# ESP8266_ATM90E26_Emon.net
KiCad netlist of a schematic drawn in EAGLE
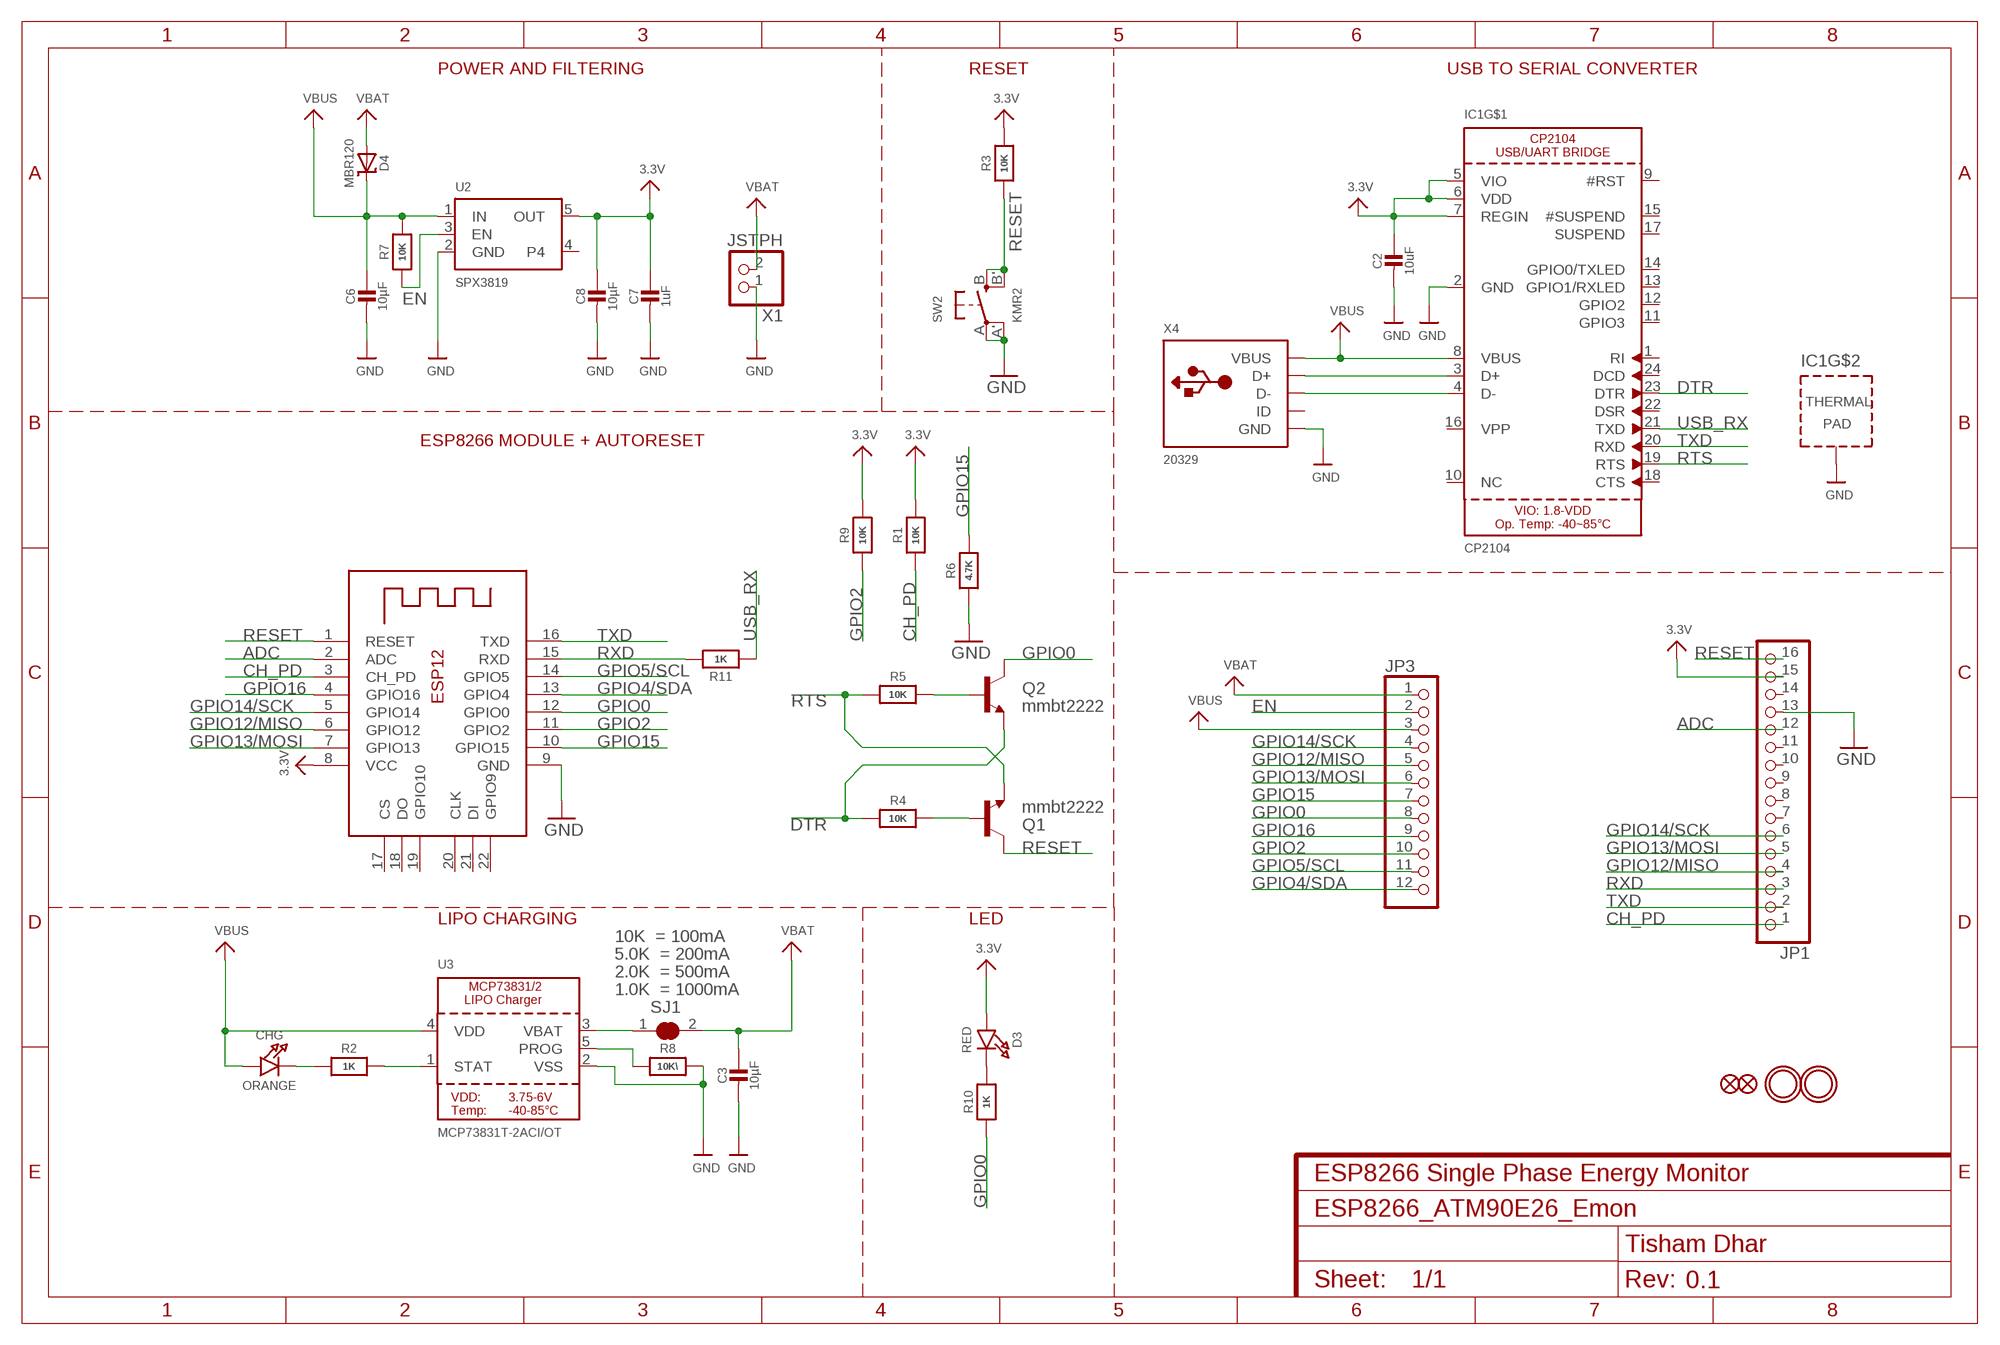
[diagram p0: schematic, sheet 1, part 1 of 2]
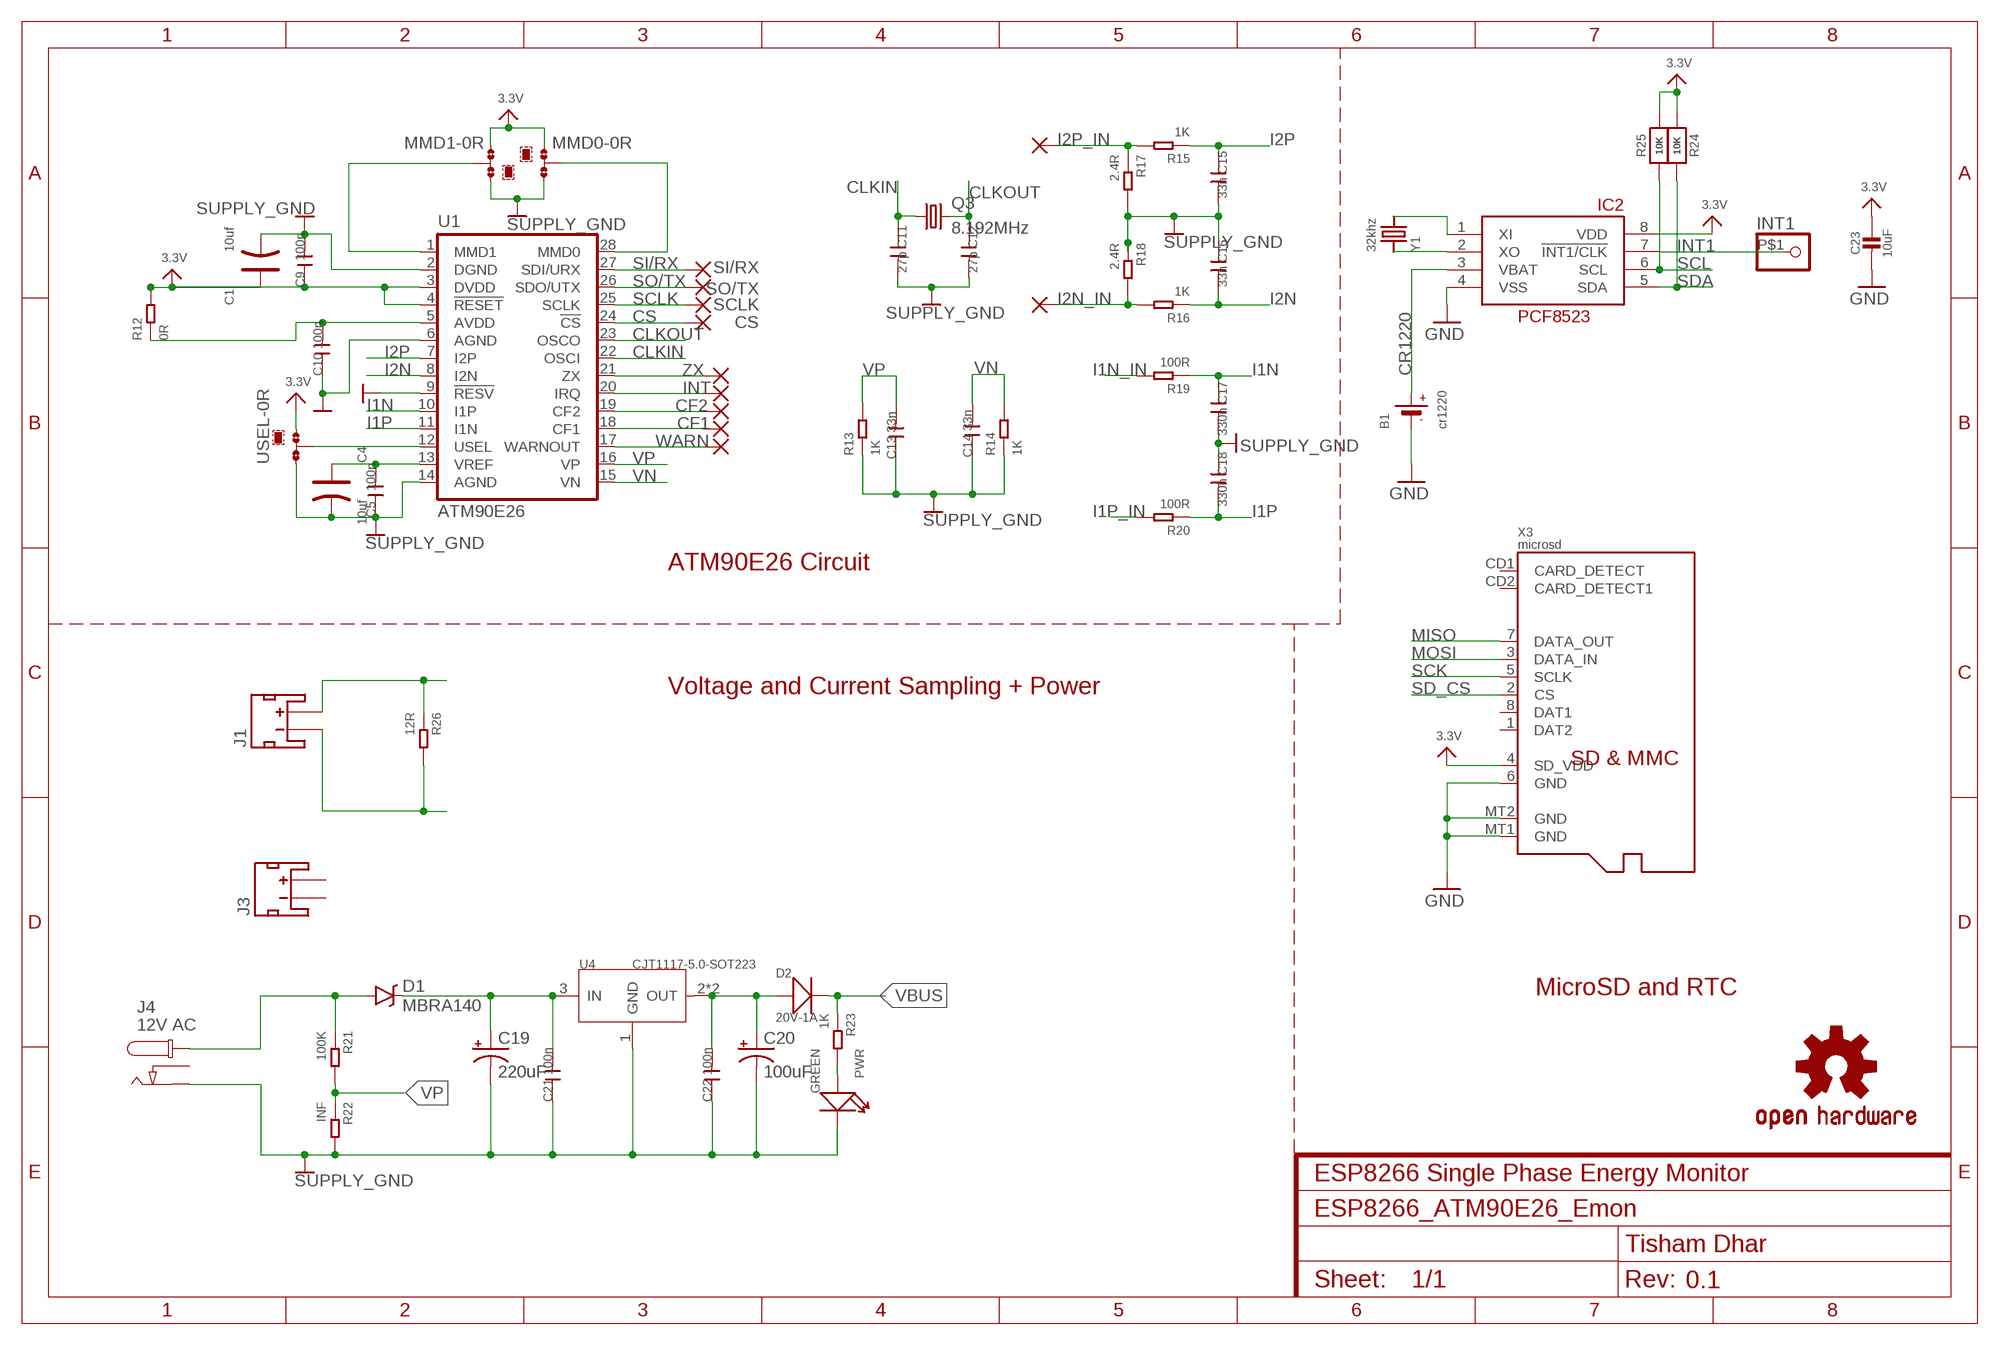
[diagram p1: schematic, sheet 1, part 2 of 2]

(export (version "E")
  (design (tool "Eeschema 10.0.6"))
  (components
    (comp (ref "B1")
      (value "cr1220")
      (footprint "eagle-import:CR1220")
      (libsource (lib "eagle-import") (part "BATTERYCR1220_SMT"))
    )
    (comp (ref "C1")
      (value "10uf")
      (footprint "eagle-import:AVX-A")
      (fields (field (name "MPN") "TAJA226*010#NJ"))
      (libsource (lib "eagle-import") (part "TANTALUM-SMD-22UF-10V(AVX-A)"))
    )
    (comp (ref "C2")
      (value "10uF")
      (footprint "eagle-import:0603-NO")
      (libsource (lib "eagle-import") (part "CAP_CERAMIC0603_NO"))
    )
    (comp (ref "C3")
      (value "10µF")
      (footprint "eagle-import:0603-NO")
      (libsource (lib "eagle-import") (part "CAP_CERAMIC0603_NO"))
    )
    (comp (ref "C4")
      (value "10uf")
      (footprint "eagle-import:AVX-A")
      (fields (field (name "MPN") "TAJA226*010#NJ"))
      (libsource (lib "eagle-import") (part "TANTALUM-SMD-22UF-10V(AVX-A)"))
    )
    (comp (ref "C5")
      (value "100n")
      (footprint "eagle-import:C0603")
      (libsource (lib "eagle-import") (part "C-0603"))
    )
    (comp (ref "C6")
      (value "10µF")
      (footprint "eagle-import:0603-NO")
      (libsource (lib "eagle-import") (part "CAP_CERAMIC0603_NO"))
    )
    (comp (ref "C7")
      (value "1uF")
      (footprint "eagle-import:0603-NO")
      (libsource (lib "eagle-import") (part "CAP_CERAMIC0603_NO"))
    )
    (comp (ref "C8")
      (value "10µF")
      (footprint "eagle-import:0603-NO")
      (libsource (lib "eagle-import") (part "CAP_CERAMIC0603_NO"))
    )
    (comp (ref "C9")
      (value "100n")
      (footprint "eagle-import:C0603")
      (libsource (lib "eagle-import") (part "C-0603"))
    )
    (comp (ref "C10")
      (value "100n")
      (footprint "eagle-import:C0603")
      (libsource (lib "eagle-import") (part "C-0603"))
    )
    (comp (ref "C11")
      (value "27p")
      (footprint "eagle-import:C0603")
      (libsource (lib "eagle-import") (part "C-0603"))
    )
    (comp (ref "C12")
      (value "27p")
      (footprint "eagle-import:C0603")
      (libsource (lib "eagle-import") (part "C-0603"))
    )
    (comp (ref "C13")
      (value "33n")
      (footprint "eagle-import:C0603")
      (libsource (lib "eagle-import") (part "C-0603"))
    )
    (comp (ref "C14")
      (value "33n")
      (footprint "eagle-import:C0603")
      (libsource (lib "eagle-import") (part "C-0603"))
    )
    (comp (ref "C15")
      (value "33n")
      (footprint "eagle-import:C0603")
      (libsource (lib "eagle-import") (part "C-0603"))
    )
    (comp (ref "C16")
      (value "33n")
      (footprint "eagle-import:C0603")
      (libsource (lib "eagle-import") (part "C-0603"))
    )
    (comp (ref "C17")
      (value "330n")
      (footprint "eagle-import:C0603")
      (libsource (lib "eagle-import") (part "C-0603"))
    )
    (comp (ref "C18")
      (value "330n")
      (footprint "eagle-import:C0603")
      (libsource (lib "eagle-import") (part "C-0603"))
    )
    (comp (ref "C19")
      (value "220uF")
      (footprint "eagle-import:140CLH-1010")
      (libsource (lib "eagle-import") (part "CPOL-US140CLH-1010"))
    )
    (comp (ref "C20")
      (value "100uF")
      (footprint "eagle-import:153CLV-0605")
      (libsource (lib "eagle-import") (part "CPOL-US153CLV-0605"))
    )
    (comp (ref "C21")
      (value "100n")
      (footprint "eagle-import:C0603")
      (libsource (lib "eagle-import") (part "C-0603"))
    )
    (comp (ref "C22")
      (value "100n")
      (footprint "eagle-import:C0603")
      (libsource (lib "eagle-import") (part "C-0603"))
    )
    (comp (ref "C23")
      (value "10uF")
      (footprint "eagle-import:0603-NO")
      (libsource (lib "eagle-import") (part "CAP_CERAMIC0603_NO"))
    )
    (comp (ref "CF1")
      (value "WIREPADSMD1,27-254")
      (footprint "eagle-import:SMD1,27-2,54")
      (libsource (lib "eagle-import") (part "WIREPADSMD1,27-254"))
    )
    (comp (ref "CF2")
      (value "WIREPADSMD1,27-254")
      (footprint "eagle-import:SMD1,27-2,54")
      (libsource (lib "eagle-import") (part "WIREPADSMD1,27-254"))
    )
    (comp (ref "CHG")
      (value "ORANGE")
      (footprint "eagle-import:CHIPLED_0603_NOOUTLINE")
      (libsource (lib "eagle-import") (part "LED0603_NOOUTLINE"))
    )
    (comp (ref "CS")
      (value "WIREPADSMD1,27-254")
      (footprint "eagle-import:SMD1,27-2,54")
      (libsource (lib "eagle-import") (part "WIREPADSMD1,27-254"))
    )
    (comp (ref "D1")
      (value "MBRA140")
      (footprint "eagle-import:SMA-DIODE")
      (libsource (lib "eagle-import") (part "MBRA140"))
    )
    (comp (ref "D2")
      (value "20V-1A")
      (footprint "eagle-import:SOD-123")
      (fields (field (name "MPN") "B5819W"))
      (libsource (lib "eagle-import") (part "SMD-DIODE-SCHOTTKY-20V-1A(SOD-123)"))
    )
    (comp (ref "D3")
      (value "RED")
      (footprint "eagle-import:CHIPLED_0805_NOOUTLINE")
      (libsource (lib "eagle-import") (part "LED0805_NOOUTLINE"))
    )
    (comp (ref "D4")
      (value "MBR120")
      (footprint "eagle-import:SOD-123")
      (libsource (lib "eagle-import") (part "DIODE-SCHOTTKYSOD-123"))
    )
    (comp (ref "I2N_IN")
      (value "WIREPADSMD1,27-254")
      (footprint "eagle-import:SMD1,27-2,54")
      (libsource (lib "eagle-import") (part "WIREPADSMD1,27-254"))
    )
    (comp (ref "I2P_IN")
      (value "WIREPADSMD1,27-254")
      (footprint "eagle-import:SMD1,27-2,54")
      (libsource (lib "eagle-import") (part "WIREPADSMD1,27-254"))
    )
    (comp (ref "IC1")
      (value "CP2104")
      (footprint "eagle-import:QFN24_4MM_SMSC")
      (libsource (lib "eagle-import") (part "CP2104"))
    )
    (comp (ref "IC2")
      (value "RTC_PCF8523T")
      (footprint "eagle-import:SOIC8_150MIL")
      (libsource (lib "eagle-import") (part "RTC_PCF8523T"))
    )
    (comp (ref "INT")
      (value "WIREPADSMD1,27-254")
      (footprint "eagle-import:SMD1,27-2,54")
      (libsource (lib "eagle-import") (part "WIREPADSMD1,27-254"))
    )
    (comp (ref "INT1")
      (value "HEADER-1X1-SMD-MASKHELD_1X2MM")
      (footprint "eagle-import:1X01_SMD_MASKHELD_1X2MM")
      (libsource (lib "eagle-import") (part "HEADER-1X1-SMD-MASKHELD_1X2MM"))
    )
    (comp (ref "J1")
      (value "JST_2MM_MALE")
      (footprint "eagle-import:JST-2-SMD")
      (libsource (lib "eagle-import") (part "JST_2MM_MALE"))
    )
    (comp (ref "J3")
      (value "JST_2MM_MALE")
      (footprint "eagle-import:JST-2-SMD")
      (libsource (lib "eagle-import") (part "JST_2MM_MALE"))
    )
    (comp (ref "J4")
      (value "12V AC")
      (footprint "eagle-import:DC_BARREL_JACK_SMD_2MM")
      (libsource (lib "eagle-import") (part "CON_DC_M-DC_SMD"))
    )
    (comp (ref "JP1")
      (value "HEADER-1X16ROUND")
      (footprint "eagle-import:1X16_ROUND")
      (libsource (lib "eagle-import") (part "HEADER-1X16ROUND"))
    )
    (comp (ref "JP3")
      (value "HEADER-1X12")
      (footprint "eagle-import:1X12_ROUND")
      (libsource (lib "eagle-import") (part "HEADER-1X12"))
    )
    (comp (ref "LOGO1")
      (value "OSHW-LOGOS")
      (footprint "eagle-import:OSHW-LOGO-S")
      (libsource (lib "eagle-import") (part "OSHW-LOGOS"))
    )
    (comp (ref "MMD0")
      (value "0R-JUMPA")
      (footprint "eagle-import:A0R-JMP")
      (libsource (lib "eagle-import") (part "0R-JUMPA"))
    )
    (comp (ref "MMD1")
      (value "0R-JUMPA")
      (footprint "eagle-import:A0R-JMP")
      (libsource (lib "eagle-import") (part "0R-JUMPA"))
    )
    (comp (ref "PWR")
      (value "GREEN")
      (footprint "eagle-import:LED-0603")
      (libsource (lib "eagle-import") (part "LED'0603'"))
    )
    (comp (ref "Q1")
      (value "mmbt2222")
      (footprint "eagle-import:SOT23-3")
      (libsource (lib "eagle-import") (part "TRANSISTOR_NPNSOT23-3"))
    )
    (comp (ref "Q2")
      (value "mmbt2222")
      (footprint "eagle-import:SOT23-3")
      (libsource (lib "eagle-import") (part "TRANSISTOR_NPNSOT23-3"))
    )
    (comp (ref "Q3")
      (value "8.192MHz")
      (footprint "eagle-import:HC49UP")
      (libsource (lib "eagle-import") (part "CRYSTALHC49UP"))
    )
    (comp (ref "R1")
      (value "10K")
      (footprint "eagle-import:0603-NO")
      (libsource (lib "eagle-import") (part "RESISTOR_0603_NOOUT"))
    )
    (comp (ref "R2")
      (value "1K")
      (footprint "eagle-import:0603-NO")
      (libsource (lib "eagle-import") (part "RESISTOR_0603_NOOUT"))
    )
    (comp (ref "R3")
      (value "10K")
      (footprint "eagle-import:0603-NO")
      (libsource (lib "eagle-import") (part "RESISTOR_0603_NOOUT"))
    )
    (comp (ref "R4")
      (value "10K")
      (footprint "eagle-import:0603-NO")
      (libsource (lib "eagle-import") (part "RESISTOR_0603_NOOUT"))
    )
    (comp (ref "R5")
      (value "10K")
      (footprint "eagle-import:_0603MP")
      (libsource (lib "eagle-import") (part "RESISTOR_0603MP"))
    )
    (comp (ref "R6")
      (value "4.7K")
      (footprint "eagle-import:0603-NO")
      (libsource (lib "eagle-import") (part "RESISTOR_0603_NOOUT"))
    )
    (comp (ref "R7")
      (value "10K")
      (footprint "eagle-import:0603-NO")
      (libsource (lib "eagle-import") (part "RESISTOR_0603_NOOUT"))
    )
    (comp (ref "R8")
      (value "10K\\")
      (footprint "eagle-import:0603-NO")
      (libsource (lib "eagle-import") (part "RESISTOR_0603_NOOUT"))
    )
    (comp (ref "R9")
      (value "10K")
      (footprint "eagle-import:0603-NO")
      (libsource (lib "eagle-import") (part "RESISTOR_0603_NOOUT"))
    )
    (comp (ref "R10")
      (value "1K")
      (footprint "eagle-import:0603-NO")
      (libsource (lib "eagle-import") (part "RESISTOR_0603_NOOUT"))
    )
    (comp (ref "R11")
      (value "1K")
      (footprint "eagle-import:_0603MP")
      (libsource (lib "eagle-import") (part "RESISTOR_0603MP"))
    )
    (comp (ref "R12")
      (value "0R")
      (footprint "eagle-import:R0603")
      (fields (field (name "MPN") "RC0603JR-070RL"))
      (libsource (lib "eagle-import") (part "SMD-RES-0R(0603)"))
    )
    (comp (ref "R13")
      (value "1K")
      (footprint "eagle-import:R0603")
      (fields (field (name "MPN") "RC0603FR-071KL"))
      (libsource (lib "eagle-import") (part "SMD-RES-1K(0603)"))
    )
    (comp (ref "R14")
      (value "1K")
      (footprint "eagle-import:R0603")
      (fields (field (name "MPN") "RC0603FR-071KL"))
      (libsource (lib "eagle-import") (part "SMD-RES-1K(0603)"))
    )
    (comp (ref "R15")
      (value "1K")
      (footprint "eagle-import:R0603")
      (fields (field (name "MPN") "RC0603FR-071KL"))
      (libsource (lib "eagle-import") (part "SMD-RES-1K(0603)"))
    )
    (comp (ref "R16")
      (value "1K")
      (footprint "eagle-import:R0603")
      (fields (field (name "MPN") "RC0603FR-071KL"))
      (libsource (lib "eagle-import") (part "SMD-RES-1K(0603)"))
    )
    (comp (ref "R17")
      (value "2.4R")
      (footprint "eagle-import:R0603")
      (fields (field (name "MPN") "RC0603FR-071KL"))
      (libsource (lib "eagle-import") (part "SMD-RES-1K(0603)"))
    )
    (comp (ref "R18")
      (value "2.4R")
      (footprint "eagle-import:R0603")
      (fields (field (name "MPN") "RC0603FR-071KL"))
      (libsource (lib "eagle-import") (part "SMD-RES-1K(0603)"))
    )
    (comp (ref "R19")
      (value "100R")
      (footprint "eagle-import:R0603")
      (fields (field (name "MPN") "RC0603FR-071KL"))
      (libsource (lib "eagle-import") (part "SMD-RES-1K(0603)"))
    )
    (comp (ref "R20")
      (value "100R")
      (footprint "eagle-import:R0603")
      (fields (field (name "MPN") "RC0603FR-071KL"))
      (libsource (lib "eagle-import") (part "SMD-RES-1K(0603)"))
    )
    (comp (ref "R21")
      (value "100K")
      (footprint "eagle-import:R0603")
      (fields (field (name "MPN") "RC0603JR-070RL"))
      (libsource (lib "eagle-import") (part "SMD-RES-0R(0603)"))
    )
    (comp (ref "R22")
      (value "INF")
      (footprint "eagle-import:R0603")
      (fields (field (name "MPN") "RC0603JR-070RL"))
      (libsource (lib "eagle-import") (part "SMD-RES-0R(0603)"))
    )
    (comp (ref "R23")
      (value "1K")
      (footprint "eagle-import:R0603")
      (fields (field (name "MPN") "RC0603JR-070RL"))
      (libsource (lib "eagle-import") (part "SMD-RES-0R(0603)"))
    )
    (comp (ref "R24")
      (value "10K")
      (footprint "eagle-import:0603-NO")
      (libsource (lib "eagle-import") (part "RESISTOR_0603_NOOUT"))
    )
    (comp (ref "R25")
      (value "10K")
      (footprint "eagle-import:0603-NO")
      (libsource (lib "eagle-import") (part "RESISTOR_0603_NOOUT"))
    )
    (comp (ref "R26")
      (value "12R")
      (footprint "eagle-import:R0603")
      (fields (field (name "MPN") "RC0603JR-070RL"))
      (libsource (lib "eagle-import") (part "SMD-RES-0R(0603)"))
    )
    (comp (ref "SCLK")
      (value "WIREPADSMD1,27-254")
      (footprint "eagle-import:SMD1,27-2,54")
      (libsource (lib "eagle-import") (part "WIREPADSMD1,27-254"))
    )
    (comp (ref "SI/RX")
      (value "WIREPADSMD1,27-254")
      (footprint "eagle-import:SMD1,27-2,54")
      (libsource (lib "eagle-import") (part "WIREPADSMD1,27-254"))
    )
    (comp (ref "SJ1")
      (value "SOLDERJUMPER_CLOSED")
      (footprint "eagle-import:SOLDERJUMPER_CLOSEDWIRE")
      (libsource (lib "eagle-import") (part "SOLDERJUMPER_CLOSED"))
    )
    (comp (ref "SO/TX")
      (value "WIREPADSMD1,27-254")
      (footprint "eagle-import:SMD1,27-2,54")
      (libsource (lib "eagle-import") (part "WIREPADSMD1,27-254"))
    )
    (comp (ref "SW2")
      (value "KMR2")
      (footprint "eagle-import:BTN_KMR2_4.6X2.8")
      (libsource (lib "eagle-import") (part "SWITCH_TACT_SMT4.6X2.8"))
    )
    (comp (ref "U$31")
      (value "MOUNTINGHOLE2.5")
      (footprint "eagle-import:MOUNTINGHOLE_2.5_PLATED")
      (libsource (lib "eagle-import") (part "MOUNTINGHOLE2.5"))
    )
    (comp (ref "U$32")
      (value "MOUNTINGHOLE2.5")
      (footprint "eagle-import:MOUNTINGHOLE_2.5_PLATED")
      (libsource (lib "eagle-import") (part "MOUNTINGHOLE2.5"))
    )
    (comp (ref "U$34")
      (value "FIDUCIAL\"\"")
      (footprint "eagle-import:FIDUCIAL_1MM")
      (libsource (lib "eagle-import") (part "FIDUCIAL{dblquote}{dblquote}"))
    )
    (comp (ref "U$35")
      (value "FIDUCIAL\"\"")
      (footprint "eagle-import:FIDUCIAL_1MM")
      (libsource (lib "eagle-import") (part "FIDUCIAL{dblquote}{dblquote}"))
    )
    (comp (ref "U1")
      (value "ATM90E26")
      (footprint "eagle-import:SSOP-28")
      (libsource (lib "eagle-import") (part "ATM90E26"))
    )
    (comp (ref "U2")
      (value "SPX3819")
      (footprint "eagle-import:SOT23-5")
      (libsource (lib "eagle-import") (part "VREG_SOT23-5"))
    )
    (comp (ref "U3")
      (value "MCP73831T-2ACI/OT")
      (footprint "eagle-import:SOT23-5")
      (libsource (lib "eagle-import") (part "MCP73831/2"))
    )
    (comp (ref "U4")
      (value "CJT1117-5.0-SOT223")
      (footprint "eagle-import:SOT-223")
      (fields (field (name "MPN") "CJT1117-5.0"))
      (libsource (lib "eagle-import") (part "PMIC-CJT1117-5.0(SOT223)"))
    )
    (comp (ref "USEL")
      (value "0R-JUMPA")
      (footprint "eagle-import:A0R-JMP")
      (libsource (lib "eagle-import") (part "0R-JUMPA"))
    )
    (comp (ref "WARN")
      (value "WIREPADSMD1,27-254")
      (footprint "eagle-import:SMD1,27-2,54")
      (libsource (lib "eagle-import") (part "WIREPADSMD1,27-254"))
    )
    (comp (ref "X1")
      (value "JSTPH")
      (footprint "eagle-import:JSTPH2")
      (libsource (lib "eagle-import") (part "CON_JST_PH_2PIN"))
    )
    (comp (ref "X2")
      (value "ESP-12")
      (footprint "eagle-import:ESP-12E")
      (libsource (lib "eagle-import") (part "ESP-12E"))
    )
    (comp (ref "X3")
      (value "microsd")
      (footprint "eagle-import:MICROSD")
      (libsource (lib "eagle-import") (part "MICROSD"))
    )
    (comp (ref "X4")
      (value "20329")
      (footprint "eagle-import:4UCONN_20329_V2")
      (libsource (lib "eagle-import") (part "USB_MICRO_20329_V2"))
    )
    (comp (ref "Y1")
      (value "32khz")
      (footprint "eagle-import:CRYSTAL_8X3.8")
      (libsource (lib "eagle-import") (part "CRYSTAL8.0X3.8"))
    )
    (comp (ref "ZX")
      (value "WIREPADSMD1,27-254")
      (footprint "eagle-import:SMD1,27-2,54")
      (libsource (lib "eagle-import") (part "WIREPADSMD1,27-254"))
    )
  )
  (nets
    (net (code "1") (name "/ADC") (class "Default")
      (node (ref "JP1") (pin "12") (pinfunction "12_12") (pintype "passive"))
      (node (ref "X2") (pin "2") (pinfunction "ADC_2") (pintype "passive"))
    )
    (net (code "2") (name "/CH_PD") (class "Default")
      (node (ref "JP1") (pin "1") (pinfunction "1_1") (pintype "passive"))
      (node (ref "R1") (pin "1") (pinfunction "1_1") (pintype "passive"))
      (node (ref "X2") (pin "3") (pinfunction "CH_PD_3") (pintype "input"))
    )
    (net (code "3") (name "/CLKIN") (class "Default")
      (node (ref "C11") (pin "1") (pinfunction "1_1") (pintype "passive"))
      (node (ref "Q3") (pin "1") (pinfunction "1_1") (pintype "passive"))
      (node (ref "U1") (pin "22") (pinfunction "OSCI_22") (pintype "input"))
    )
    (net (code "4") (name "/CLKOUT") (class "Default")
      (node (ref "C12") (pin "1") (pinfunction "1_1") (pintype "passive"))
      (node (ref "Q3") (pin "2") (pinfunction "2_2") (pintype "passive"))
      (node (ref "U1") (pin "23") (pinfunction "OSCO_23") (pintype "output"))
    )
    (net (code "5") (name "/CR1220") (class "Default")
      (node (ref "B1") (pin "+$1") (pinfunction "+_+$1") (pintype "passive"))
      (node (ref "IC2") (pin "3") (pinfunction "VBAT_3") (pintype "power_in"))
    )
    (net (code "6") (name "/CS") (class "Default")
      (node (ref "CS") (pin "1") (pinfunction "P_1") (pintype "passive"))
      (node (ref "U1") (pin "24") (pinfunction "~{CS}_24") (pintype "input"))
    )
    (net (code "7") (name "/DTR") (class "Default")
      (node (ref "IC1") (pin "23") (pinfunction "DTR_23") (pintype "output"))
      (node (ref "Q2") (pin "2") (pinfunction "E_2") (pintype "passive"))
      (node (ref "R4") (pin "1") (pinfunction "1_1") (pintype "passive"))
    )
    (net (code "8") (name "/EN") (class "Default")
      (node (ref "JP3") (pin "2") (pinfunction "2_2") (pintype "passive"))
      (node (ref "R7") (pin "1") (pinfunction "1_1") (pintype "passive"))
      (node (ref "U2") (pin "3") (pinfunction "EN_3") (pintype "input"))
    )
    (net (code "9") (name "/GPIO0") (class "Default")
      (node (ref "JP3") (pin "8") (pinfunction "8_8") (pintype "passive"))
      (node (ref "Q2") (pin "3") (pinfunction "C_3") (pintype "passive"))
      (node (ref "R10") (pin "1") (pinfunction "1_1") (pintype "passive"))
      (node (ref "X2") (pin "12") (pinfunction "GPIO0_12") (pintype "bidirectional"))
    )
    (net (code "10") (name "/GPIO2") (class "Default")
      (node (ref "JP3") (pin "10") (pinfunction "10_10") (pintype "passive"))
      (node (ref "R9") (pin "1") (pinfunction "1_1") (pintype "passive"))
      (node (ref "X2") (pin "11") (pinfunction "GPIO2_11") (pintype "bidirectional"))
    )
    (net (code "11") (name "/GPIO4{slash}SDA") (class "Default")
      (node (ref "JP3") (pin "12") (pinfunction "12_12") (pintype "passive"))
      (node (ref "X2") (pin "13") (pinfunction "GPIO4_13") (pintype "bidirectional"))
    )
    (net (code "12") (name "/GPIO5{slash}SCL") (class "Default")
      (node (ref "JP3") (pin "11") (pinfunction "11_11") (pintype "passive"))
      (node (ref "X2") (pin "14") (pinfunction "GPIO5_14") (pintype "bidirectional"))
    )
    (net (code "13") (name "/GPIO12{slash}MISO") (class "Default")
      (node (ref "JP1") (pin "4") (pinfunction "4_4") (pintype "passive"))
      (node (ref "JP3") (pin "5") (pinfunction "5_5") (pintype "passive"))
      (node (ref "X2") (pin "6") (pinfunction "GPIO12_6") (pintype "bidirectional"))
    )
    (net (code "14") (name "/GPIO13{slash}MOSI") (class "Default")
      (node (ref "JP1") (pin "5") (pinfunction "5_5") (pintype "passive"))
      (node (ref "JP3") (pin "6") (pinfunction "6_6") (pintype "passive"))
      (node (ref "X2") (pin "7") (pinfunction "GPIO13_7") (pintype "bidirectional"))
    )
    (net (code "15") (name "/GPIO14{slash}SCK") (class "Default")
      (node (ref "JP1") (pin "6") (pinfunction "6_6") (pintype "passive"))
      (node (ref "JP3") (pin "4") (pinfunction "4_4") (pintype "passive"))
      (node (ref "X2") (pin "5") (pinfunction "GPIO14_5") (pintype "bidirectional"))
    )
    (net (code "16") (name "/GPIO15") (class "Default")
      (node (ref "JP3") (pin "7") (pinfunction "7_7") (pintype "passive"))
      (node (ref "R6") (pin "2") (pinfunction "2_2") (pintype "passive"))
      (node (ref "X2") (pin "10") (pinfunction "GPIO15_10") (pintype "bidirectional"))
    )
    (net (code "17") (name "/GPIO16") (class "Default")
      (node (ref "JP3") (pin "9") (pinfunction "9_9") (pintype "passive"))
      (node (ref "X2") (pin "4") (pinfunction "GPIO16_4") (pintype "bidirectional"))
    )
    (net (code "18") (name "/I1N") (class "Default")
      (node (ref "C17") (pin "1") (pinfunction "1_1") (pintype "passive"))
      (node (ref "R19") (pin "1") (pinfunction "1_1") (pintype "passive"))
      (node (ref "U1") (pin "10") (pinfunction "I1P_10") (pintype "input"))
    )
    (net (code "19") (name "/I1N_IN") (class "Default")
      (node (ref "R19") (pin "2") (pinfunction "2_2") (pintype "passive"))
    )
    (net (code "20") (name "/I1P") (class "Default")
      (node (ref "C18") (pin "2") (pinfunction "2_2") (pintype "passive"))
      (node (ref "R20") (pin "1") (pinfunction "1_1") (pintype "passive"))
      (node (ref "U1") (pin "11") (pinfunction "I1N_11") (pintype "input"))
    )
    (net (code "21") (name "/I1P_IN") (class "Default")
      (node (ref "R20") (pin "2") (pinfunction "2_2") (pintype "passive"))
    )
    (net (code "22") (name "/I2N") (class "Default")
      (node (ref "C16") (pin "2") (pinfunction "2_2") (pintype "passive"))
      (node (ref "R16") (pin "1") (pinfunction "1_1") (pintype "passive"))
      (node (ref "U1") (pin "8") (pinfunction "I2N_8") (pintype "input"))
    )
    (net (code "23") (name "/I2N_IN") (class "Default")
      (node (ref "I2N_IN") (pin "1") (pinfunction "P_1") (pintype "passive"))
      (node (ref "R16") (pin "2") (pinfunction "2_2") (pintype "passive"))
      (node (ref "R18") (pin "2") (pinfunction "2_2") (pintype "passive"))
    )
    (net (code "24") (name "/I2P") (class "Default")
      (node (ref "C15") (pin "1") (pinfunction "1_1") (pintype "passive"))
      (node (ref "R15") (pin "1") (pinfunction "1_1") (pintype "passive"))
      (node (ref "U1") (pin "7") (pinfunction "I2P_7") (pintype "input"))
    )
    (net (code "25") (name "/I2P_IN") (class "Default")
      (node (ref "I2P_IN") (pin "1") (pinfunction "P_1") (pintype "passive"))
      (node (ref "R15") (pin "2") (pinfunction "2_2") (pintype "passive"))
      (node (ref "R17") (pin "1") (pinfunction "1_1") (pintype "passive"))
    )
    (net (code "26") (name "/INT1") (class "Default")
      (node (ref "IC2") (pin "7") (pinfunction "~{INT1/CLK}_7") (pintype "output"))
      (node (ref "INT1") (pin "P$1") (pinfunction "1_P$1") (pintype "passive"))
    )
    (net (code "27") (name "/MISO") (class "Default")
      (node (ref "X3") (pin "7") (pinfunction "DATA_OUT_7") (pintype "output"))
    )
    (net (code "28") (name "/MOSI") (class "Default")
      (node (ref "X3") (pin "3") (pinfunction "DATA_IN_3") (pintype "input"))
    )
    (net (code "29") (name "/RESET") (class "Default")
      (node (ref "JP1") (pin "16") (pinfunction "16_16") (pintype "passive"))
      (node (ref "Q1") (pin "3") (pinfunction "C_3") (pintype "passive"))
      (node (ref "R3") (pin "1") (pinfunction "1_1") (pintype "passive"))
      (node (ref "SW2") (pin "B") (pinfunction "S_B") (pintype "passive"))
      (node (ref "SW2") (pin "B'") (pinfunction "S1_B'") (pintype "passive"))
      (node (ref "X2") (pin "1") (pinfunction "RESET_1") (pintype "input"))
    )
    (net (code "30") (name "/RTS") (class "Default")
      (node (ref "IC1") (pin "19") (pinfunction "RTS_19") (pintype "output"))
      (node (ref "Q1") (pin "2") (pinfunction "E_2") (pintype "passive"))
      (node (ref "R5") (pin "1") (pinfunction "1_1") (pintype "passive"))
    )
    (net (code "31") (name "/RXD") (class "Default")
      (node (ref "JP1") (pin "3") (pinfunction "3_3") (pintype "passive"))
      (node (ref "R11") (pin "2") (pinfunction "2_2") (pintype "passive"))
      (node (ref "X2") (pin "15") (pinfunction "RXD_15") (pintype "input"))
    )
    (net (code "32") (name "/SCK") (class "Default")
      (node (ref "X3") (pin "5") (pinfunction "SCLK_5") (pintype "input"))
    )
    (net (code "33") (name "/SCL") (class "Default")
      (node (ref "IC2") (pin "6") (pinfunction "SCL_6") (pintype "bidirectional"))
      (node (ref "R25") (pin "1") (pinfunction "1_1") (pintype "passive"))
    )
    (net (code "34") (name "/SCLK") (class "Default")
      (node (ref "SCLK") (pin "1") (pinfunction "P_1") (pintype "passive"))
      (node (ref "U1") (pin "25") (pinfunction "SCLK_25") (pintype "input"))
    )
    (net (code "35") (name "/SDA") (class "Default")
      (node (ref "IC2") (pin "5") (pinfunction "SDA_5") (pintype "bidirectional"))
      (node (ref "R24") (pin "1") (pinfunction "1_1") (pintype "passive"))
    )
    (net (code "36") (name "/SD_CS") (class "Default")
      (node (ref "X3") (pin "2") (pinfunction "CS_2") (pintype "input"))
    )
    (net (code "37") (name "/SI{slash}RX") (class "Default")
      (node (ref "SI/RX") (pin "1") (pinfunction "P_1") (pintype "passive"))
      (node (ref "U1") (pin "27") (pinfunction "SDI/URX_27") (pintype "input"))
    )
    (net (code "38") (name "/SO{slash}TX") (class "Default")
      (node (ref "SO/TX") (pin "1") (pinfunction "P_1") (pintype "passive"))
      (node (ref "U1") (pin "26") (pinfunction "SDO/UTX_26") (pintype "output"))
    )
    (net (code "39") (name "/TXD") (class "Default")
      (node (ref "IC1") (pin "20") (pinfunction "RXD_20") (pintype "input"))
      (node (ref "JP1") (pin "2") (pinfunction "2_2") (pintype "passive"))
      (node (ref "X2") (pin "16") (pinfunction "TXD_16") (pintype "output"))
    )
    (net (code "40") (name "/USB_RX") (class "Default")
      (node (ref "IC1") (pin "21") (pinfunction "TXD_21") (pintype "output"))
      (node (ref "R11") (pin "1") (pinfunction "1_1") (pintype "passive"))
    )
    (net (code "41") (name "/VN") (class "Default")
      (node (ref "C14") (pin "2") (pinfunction "2_2") (pintype "passive"))
      (node (ref "R14") (pin "2") (pinfunction "2_2") (pintype "passive"))
      (node (ref "U1") (pin "15") (pinfunction "VN_15") (pintype "input"))
    )
    (net (code "42") (name "3.3V") (class "Default")
      (node (ref "C1") (pin "+") (pinfunction "+_+") (pintype "passive"))
      (node (ref "C2") (pin "1") (pinfunction "1_1") (pintype "passive"))
      (node (ref "C23") (pin "1") (pinfunction "1_1") (pintype "passive"))
      (node (ref "C7") (pin "1") (pinfunction "1_1") (pintype "passive"))
      (node (ref "C8") (pin "1") (pinfunction "1_1") (pintype "passive"))
      (node (ref "C9") (pin "1") (pinfunction "1_1") (pintype "passive"))
      (node (ref "D3") (pin "A") (pinfunction "A_A") (pintype "passive"))
      (node (ref "IC1") (pin "5") (pinfunction "VIO_5") (pintype "power_in"))
      (node (ref "IC1") (pin "6") (pinfunction "VDD_6") (pintype "power_in"))
      (node (ref "IC1") (pin "7") (pinfunction "REGIN_7") (pintype "power_in"))
      (node (ref "IC2") (pin "8") (pinfunction "VDD_8") (pintype "power_in"))
      (node (ref "JP1") (pin "15") (pinfunction "15_15") (pintype "passive"))
      (node (ref "MMD0") (pin "1") (pinfunction "1_1") (pintype "passive"))
      (node (ref "MMD1") (pin "2") (pinfunction "2_2") (pintype "passive"))
      (node (ref "MMD1") (pin "3") (pinfunction "3_3") (pintype "passive"))
      (node (ref "R1") (pin "2") (pinfunction "2_2") (pintype "passive"))
      (node (ref "R12") (pin "2") (pinfunction "2_2") (pintype "passive"))
      (node (ref "R24") (pin "2") (pinfunction "2_2") (pintype "passive"))
      (node (ref "R25") (pin "2") (pinfunction "2_2") (pintype "passive"))
      (node (ref "R3") (pin "2") (pinfunction "2_2") (pintype "passive"))
      (node (ref "R9") (pin "2") (pinfunction "2_2") (pintype "passive"))
      (node (ref "U1") (pin "1") (pinfunction "MMD1_1") (pintype "input"))
      (node (ref "U1") (pin "3") (pinfunction "DVDD_3") (pintype "power_in"))
      (node (ref "U1") (pin "4") (pinfunction "~{RESET}_4") (pintype "input"))
      (node (ref "U2") (pin "5") (pinfunction "OUT_5") (pintype "power_in"))
      (node (ref "USEL") (pin "1") (pinfunction "1_1") (pintype "passive"))
      (node (ref "X2") (pin "8") (pinfunction "VCC_8") (pintype "power_in"))
      (node (ref "X3") (pin "4") (pinfunction "SD_VDD_4") (pintype "power_in"))
    )
    (net (code "43") (name "GND") (class "Default")
      (node (ref "B1") (pin "-") (pinfunction "-_-") (pintype "passive"))
      (node (ref "C1") (pin "-") (pinfunction "-_-") (pintype "passive"))
      (node (ref "C10") (pin "1") (pinfunction "1_1") (pintype "passive"))
      (node (ref "C11") (pin "2") (pinfunction "2_2") (pintype "passive"))
      (node (ref "C12") (pin "2") (pinfunction "2_2") (pintype "passive"))
      (node (ref "C13") (pin "1") (pinfunction "1_1") (pintype "passive"))
      (node (ref "C14") (pin "1") (pinfunction "1_1") (pintype "passive"))
      (node (ref "C15") (pin "2") (pinfunction "2_2") (pintype "passive"))
      (node (ref "C16") (pin "1") (pinfunction "1_1") (pintype "passive"))
      (node (ref "C17") (pin "2") (pinfunction "2_2") (pintype "passive"))
      (node (ref "C18") (pin "1") (pinfunction "1_1") (pintype "passive"))
      (node (ref "C19") (pin "-") (pinfunction "-_-") (pintype "passive"))
      (node (ref "C2") (pin "2") (pinfunction "2_2") (pintype "passive"))
      (node (ref "C20") (pin "-") (pinfunction "-_-") (pintype "passive"))
      (node (ref "C21") (pin "1") (pinfunction "1_1") (pintype "passive"))
      (node (ref "C22") (pin "1") (pinfunction "1_1") (pintype "passive"))
      (node (ref "C23") (pin "2") (pinfunction "2_2") (pintype "passive"))
      (node (ref "C3") (pin "2") (pinfunction "2_2") (pintype "passive"))
      (node (ref "C4") (pin "-") (pinfunction "-_-") (pintype "passive"))
      (node (ref "C5") (pin "1") (pinfunction "1_1") (pintype "passive"))
      (node (ref "C6") (pin "2") (pinfunction "2_2") (pintype "passive"))
      (node (ref "C7") (pin "2") (pinfunction "2_2") (pintype "passive"))
      (node (ref "C8") (pin "2") (pinfunction "2_2") (pintype "passive"))
      (node (ref "C9") (pin "2") (pinfunction "2_2") (pintype "passive"))
      (node (ref "IC1") (pin "2") (pinfunction "GND_2") (pintype "power_in"))
      (node (ref "IC1") (pin "THERM") (pinfunction "TP_THERM") (pintype "power_in"))
      (node (ref "IC2") (pin "4") (pinfunction "VSS_4") (pintype "power_in"))
      (node (ref "J4") (pin "P2") (pinfunction "P2_P2") (pintype "passive"))
      (node (ref "JP1") (pin "13") (pinfunction "13_13") (pintype "passive"))
      (node (ref "MMD0") (pin "3") (pinfunction "3_3") (pintype "passive"))
      (node (ref "MMD1") (pin "1") (pinfunction "1_1") (pintype "passive"))
      (node (ref "PWR") (pin "-") (pinfunction "-_-") (pintype "passive"))
      (node (ref "R13") (pin "1") (pinfunction "1_1") (pintype "passive"))
      (node (ref "R14") (pin "1") (pinfunction "1_1") (pintype "passive"))
      (node (ref "R17") (pin "2") (pinfunction "2_2") (pintype "passive"))
      (node (ref "R18") (pin "1") (pinfunction "1_1") (pintype "passive"))
      (node (ref "R22") (pin "2") (pinfunction "2_2") (pintype "passive"))
      (node (ref "R6") (pin "1") (pinfunction "1_1") (pintype "passive"))
      (node (ref "R8") (pin "2") (pinfunction "2_2") (pintype "passive"))
      (node (ref "SW2") (pin "A") (pinfunction "P_A") (pintype "passive"))
      (node (ref "SW2") (pin "A'") (pinfunction "P1_A'") (pintype "passive"))
      (node (ref "U1") (pin "14") (pinfunction "AGND_14") (pintype "power_in"))
      (node (ref "U1") (pin "2") (pinfunction "DGND_2") (pintype "power_in"))
      (node (ref "U1") (pin "6") (pinfunction "AGND_6") (pintype "power_in"))
      (node (ref "U1") (pin "9") (pinfunction "~{RESV}_9") (pintype "input"))
      (node (ref "U2") (pin "2") (pinfunction "GND_2") (pintype "power_in"))
      (node (ref "U3") (pin "2") (pinfunction "VSS_2") (pintype "power_in"))
      (node (ref "U4") (pin "1") (pinfunction "GND_1") (pintype "bidirectional"))
      (node (ref "USEL") (pin "3") (pinfunction "3_3") (pintype "passive"))
      (node (ref "X1") (pin "1") (pinfunction "1_1") (pintype "passive"))
      (node (ref "X2") (pin "9") (pinfunction "GND_9") (pintype "power_in"))
      (node (ref "X3") (pin "6") (pinfunction "GND_6") (pintype "power_in"))
      (node (ref "X3") (pin "MT1") (pinfunction "GND_MT1") (pintype "power_in"))
      (node (ref "X3") (pin "MT2") (pinfunction "GND_MT2") (pintype "power_in"))
      (node (ref "X4") (pin "BASE@1") (pinfunction "GND_BASE@1") (pintype "power_in"))
      (node (ref "X4") (pin "BASE@2") (pinfunction "GND_BASE@2") (pintype "power_in"))
      (node (ref "X4") (pin "GND") (pinfunction "GND_GND") (pintype "power_in"))
      (node (ref "X4") (pin "SPRT@1") (pinfunction "GND_SPRT@1") (pintype "power_in"))
      (node (ref "X4") (pin "SPRT@2") (pinfunction "GND_SPRT@2") (pintype "power_in"))
      (node (ref "X4") (pin "SPRT@3") (pinfunction "GND_SPRT@3") (pintype "power_in"))
      (node (ref "X4") (pin "SPRT@4") (pinfunction "GND_SPRT@4") (pintype "power_in"))
    )
    (net (code "44") (name "Net-(C20-Pad+)") (class "Default")
      (node (ref "C20") (pin "+") (pinfunction "+_+") (pintype "passive"))
      (node (ref "C22") (pin "2") (pinfunction "2_2") (pintype "passive"))
      (node (ref "D2") (pin "+") (pinfunction "+_+") (pintype "passive"))
      (node (ref "U4") (pin "2") (pinfunction "OUT_2") (pintype "bidirectional"))
      (node (ref "U4") (pin "TER") (pinfunction "OUT_TER") (pintype "bidirectional"))
    )
    (net (code "45") (name "Net-(CF1-P)") (class "Default")
      (node (ref "CF1") (pin "1") (pinfunction "P_1") (pintype "passive"))
      (node (ref "U1") (pin "18") (pinfunction "CF1_18") (pintype "output"))
    )
    (net (code "46") (name "Net-(CF2-P)") (class "Default")
      (node (ref "CF2") (pin "1") (pinfunction "P_1") (pintype "passive"))
      (node (ref "U1") (pin "19") (pinfunction "CF2_19") (pintype "output"))
    )
    (net (code "47") (name "Net-(CHG-PadC)") (class "Default")
      (node (ref "CHG") (pin "C") (pinfunction "C_C") (pintype "passive"))
      (node (ref "R2") (pin "1") (pinfunction "1_1") (pintype "passive"))
    )
    (net (code "48") (name "Net-(D3-PadC)") (class "Default")
      (node (ref "D3") (pin "C") (pinfunction "C_C") (pintype "passive"))
      (node (ref "R10") (pin "2") (pinfunction "2_2") (pintype "passive"))
    )
    (net (code "49") (name "Net-(IC1A-D+)") (class "Default")
      (node (ref "IC1") (pin "3") (pinfunction "D+_3") (pintype "bidirectional"))
      (node (ref "X4") (pin "D+") (pinfunction "D+_D+") (pintype "bidirectional"))
    )
    (net (code "50") (name "Net-(IC1A-D-)") (class "Default")
      (node (ref "IC1") (pin "4") (pinfunction "D-_4") (pintype "bidirectional"))
      (node (ref "X4") (pin "D-") (pinfunction "D-_D-") (pintype "bidirectional"))
    )
    (net (code "51") (name "Net-(IC2-XI)") (class "Default")
      (node (ref "IC2") (pin "1") (pinfunction "XI_1") (pintype "input"))
      (node (ref "Y1") (pin "P$4") (pinfunction "2_P$4") (pintype "passive"))
    )
    (net (code "52") (name "Net-(IC2-XO)") (class "Default")
      (node (ref "IC2") (pin "2") (pinfunction "XO_2") (pintype "output"))
      (node (ref "Y1") (pin "P$1") (pinfunction "1_P$1") (pintype "passive"))
    )
    (net (code "53") (name "Net-(INT-P)") (class "Default")
      (node (ref "INT") (pin "1") (pinfunction "P_1") (pintype "passive"))
      (node (ref "U1") (pin "20") (pinfunction "IRQ_20") (pintype "output"))
    )
    (net (code "54") (name "Net-(J1-+)") (class "Default")
      (node (ref "J1") (pin "2") (pinfunction "+_2") (pintype "bidirectional"))
      (node (ref "R26") (pin "1") (pinfunction "1_1") (pintype "passive"))
    )
    (net (code "55") (name "Net-(J1--)") (class "Default")
      (node (ref "J1") (pin "1") (pinfunction "-_1") (pintype "bidirectional"))
      (node (ref "R26") (pin "2") (pinfunction "2_2") (pintype "passive"))
    )
    (net (code "56") (name "Net-(J4-P1)") (class "Default")
      (node (ref "D1") (pin "A") (pinfunction "A_A") (pintype "passive"))
      (node (ref "J4") (pin "P1@2") (pinfunction "P1_P1@2") (pintype "passive"))
      (node (ref "R21") (pin "1") (pinfunction "1_1") (pintype "passive"))
    )
    (net (code "57") (name "Net-(PWR-Pad+)") (class "Default")
      (node (ref "PWR") (pin "+") (pinfunction "+_+") (pintype "passive"))
      (node (ref "R23") (pin "2") (pinfunction "2_2") (pintype "passive"))
    )
    (net (code "58") (name "Net-(Q1-B)") (class "Default")
      (node (ref "Q1") (pin "1") (pinfunction "B_1") (pintype "passive"))
      (node (ref "R4") (pin "2") (pinfunction "2_2") (pintype "passive"))
    )
    (net (code "59") (name "Net-(Q2-B)") (class "Default")
      (node (ref "Q2") (pin "1") (pinfunction "B_1") (pintype "passive"))
      (node (ref "R5") (pin "2") (pinfunction "2_2") (pintype "passive"))
    )
    (net (code "60") (name "Net-(U1-AVDD)") (class "Default")
      (node (ref "C10") (pin "2") (pinfunction "2_2") (pintype "passive"))
      (node (ref "R12") (pin "1") (pinfunction "1_1") (pintype "passive"))
      (node (ref "U1") (pin "5") (pinfunction "AVDD_5") (pintype "power_in"))
    )
    (net (code "61") (name "Net-(U1-MMD0)") (class "Default")
      (node (ref "MMD0") (pin "2") (pinfunction "2_2") (pintype "passive"))
      (node (ref "U1") (pin "28") (pinfunction "MMD0_28") (pintype "input"))
    )
    (net (code "62") (name "Net-(U1-USEL)") (class "Default")
      (node (ref "U1") (pin "12") (pinfunction "USEL_12") (pintype "input"))
      (node (ref "USEL") (pin "2") (pinfunction "2_2") (pintype "passive"))
    )
    (net (code "63") (name "Net-(U1-VREF)") (class "Default")
      (node (ref "C4") (pin "+") (pinfunction "+_+") (pintype "passive"))
      (node (ref "C5") (pin "2") (pinfunction "2_2") (pintype "passive"))
      (node (ref "U1") (pin "13") (pinfunction "VREF_13") (pintype "power_in"))
    )
    (net (code "64") (name "Net-(U1-WARNOUT)") (class "Default")
      (node (ref "U1") (pin "17") (pinfunction "WARNOUT_17") (pintype "output"))
      (node (ref "WARN") (pin "1") (pinfunction "P_1") (pintype "passive"))
    )
    (net (code "65") (name "Net-(U1-ZX)") (class "Default")
      (node (ref "U1") (pin "21") (pinfunction "ZX_21") (pintype "bidirectional"))
      (node (ref "ZX") (pin "1") (pinfunction "P_1") (pintype "passive"))
    )
    (net (code "66") (name "Net-(U3-PROG)") (class "Default")
      (node (ref "R8") (pin "1") (pinfunction "1_1") (pintype "passive"))
      (node (ref "U3") (pin "5") (pinfunction "PROG_5") (pintype "input"))
    )
    (net (code "67") (name "Net-(U3-STAT)") (class "Default")
      (node (ref "R2") (pin "2") (pinfunction "2_2") (pintype "passive"))
      (node (ref "U3") (pin "1") (pinfunction "STAT_1") (pintype "output"))
    )
    (net (code "68") (name "Net-(U3-VBAT)") (class "Default")
      (node (ref "SJ1") (pin "1") (pinfunction "1_1") (pintype "passive"))
      (node (ref "U3") (pin "3") (pinfunction "VBAT_3") (pintype "power_in"))
    )
    (net (code "69") (name "Net-(U4-IN)") (class "Default")
      (node (ref "C19") (pin "+") (pinfunction "+_+") (pintype "passive"))
      (node (ref "C21") (pin "2") (pinfunction "2_2") (pintype "passive"))
      (node (ref "D1") (pin "C") (pinfunction "C_C") (pintype "passive"))
      (node (ref "U4") (pin "3") (pinfunction "IN_3") (pintype "bidirectional"))
    )
    (net (code "70") (name "VBAT") (class "Default")
      (node (ref "C3") (pin "1") (pinfunction "1_1") (pintype "passive"))
      (node (ref "D4") (pin "A") (pinfunction "A_A") (pintype "passive"))
      (node (ref "JP3") (pin "1") (pinfunction "1_1") (pintype "passive"))
      (node (ref "SJ1") (pin "2") (pinfunction "2_2") (pintype "passive"))
      (node (ref "X1") (pin "2") (pinfunction "2_2") (pintype "passive"))
    )
    (net (code "71") (name "VBUS") (class "Default")
      (node (ref "C6") (pin "1") (pinfunction "1_1") (pintype "passive"))
      (node (ref "CHG") (pin "A") (pinfunction "A_A") (pintype "passive"))
      (node (ref "D2") (pin "-") (pinfunction "-_-") (pintype "passive"))
      (node (ref "D4") (pin "C") (pinfunction "C_C") (pintype "passive"))
      (node (ref "IC1") (pin "8") (pinfunction "VBUS_8") (pintype "power_in"))
      (node (ref "JP3") (pin "3") (pinfunction "3_3") (pintype "passive"))
      (node (ref "R23") (pin "1") (pinfunction "1_1") (pintype "passive"))
      (node (ref "R7") (pin "2") (pinfunction "2_2") (pintype "passive"))
      (node (ref "U2") (pin "1") (pinfunction "IN_1") (pintype "power_in"))
      (node (ref "U3") (pin "4") (pinfunction "VDD_4") (pintype "power_in"))
      (node (ref "X4") (pin "VBUS") (pinfunction "VBUS_VBUS") (pintype "power_in"))
    )
    (net (code "72") (name "VP") (class "Default")
      (node (ref "C13") (pin "2") (pinfunction "2_2") (pintype "passive"))
      (node (ref "R13") (pin "2") (pinfunction "2_2") (pintype "passive"))
      (node (ref "R21") (pin "2") (pinfunction "2_2") (pintype "passive"))
      (node (ref "R22") (pin "1") (pinfunction "1_1") (pintype "passive"))
      (node (ref "U1") (pin "16") (pinfunction "VP_16") (pintype "input"))
    )
    (net (code "73") (name "unconnected-(IC1A-#RST-Pad9)") (class "Default")
      (node (ref "IC1") (pin "9") (pinfunction "#RST_9") (pintype "bidirectional"))
    )
    (net (code "74") (name "unconnected-(IC1A-#SUSPEND-Pad15)") (class "Default")
      (node (ref "IC1") (pin "15") (pinfunction "#SUSPEND_15") (pintype "output"))
    )
    (net (code "75") (name "unconnected-(IC1A-CTS-Pad18)") (class "Default")
      (node (ref "IC1") (pin "18") (pinfunction "CTS_18") (pintype "input"))
    )
    (net (code "76") (name "unconnected-(IC1A-DCD-Pad24)") (class "Default")
      (node (ref "IC1") (pin "24") (pinfunction "DCD_24") (pintype "input"))
    )
    (net (code "77") (name "unconnected-(IC1A-DSR-Pad22)") (class "Default")
      (node (ref "IC1") (pin "22") (pinfunction "DSR_22") (pintype "input"))
    )
    (net (code "78") (name "unconnected-(IC1A-GPIO0{slash}TXLED-Pad14)") (class "Default")
      (node (ref "IC1") (pin "14") (pinfunction "GPIO0/TXLED_14") (pintype "bidirectional"))
    )
    (net (code "79") (name "unconnected-(IC1A-GPIO1{slash}RXLED-Pad13)") (class "Default")
      (node (ref "IC1") (pin "13") (pinfunction "GPIO1/RXLED_13") (pintype "bidirectional"))
    )
    (net (code "80") (name "unconnected-(IC1A-GPIO2-Pad12)") (class "Default")
      (node (ref "IC1") (pin "12") (pinfunction "GPIO2_12") (pintype "bidirectional"))
    )
    (net (code "81") (name "unconnected-(IC1A-GPIO3-Pad11)") (class "Default")
      (node (ref "IC1") (pin "11") (pinfunction "GPIO3_11") (pintype "bidirectional"))
    )
    (net (code "82") (name "unconnected-(IC1A-NC-Pad10)") (class "Default")
      (node (ref "IC1") (pin "10") (pinfunction "NC_10") (pintype "no_connect"))
    )
    (net (code "83") (name "unconnected-(IC1A-RI-Pad1)") (class "Default")
      (node (ref "IC1") (pin "1") (pinfunction "RI_1") (pintype "input"))
    )
    (net (code "84") (name "unconnected-(IC1A-SUSPEND-Pad17)") (class "Default")
      (node (ref "IC1") (pin "17") (pinfunction "SUSPEND_17") (pintype "output"))
    )
    (net (code "85") (name "unconnected-(IC1A-VPP-Pad16)") (class "Default")
      (node (ref "IC1") (pin "16") (pinfunction "VPP_16") (pintype "bidirectional"))
    )
    (net (code "86") (name "unconnected-(J1-PAD1-PadNC1)") (class "Default")
      (node (ref "J1") (pin "NC1") (pinfunction "PAD1_NC1") (pintype "bidirectional"))
    )
    (net (code "87") (name "unconnected-(J1-PAD2-PadNC2)") (class "Default")
      (node (ref "J1") (pin "NC2") (pinfunction "PAD2_NC2") (pintype "bidirectional"))
    )
    (net (code "88") (name "unconnected-(J3-+-Pad2)") (class "Default")
      (node (ref "J3") (pin "2") (pinfunction "+_2") (pintype "bidirectional"))
    )
    (net (code "89") (name "unconnected-(J3---Pad1)") (class "Default")
      (node (ref "J3") (pin "1") (pinfunction "-_1") (pintype "bidirectional"))
    )
    (net (code "90") (name "unconnected-(J3-PAD1-PadNC1)") (class "Default")
      (node (ref "J3") (pin "NC1") (pinfunction "PAD1_NC1") (pintype "bidirectional"))
    )
    (net (code "91") (name "unconnected-(J3-PAD2-PadNC2)") (class "Default")
      (node (ref "J3") (pin "NC2") (pinfunction "PAD2_NC2") (pintype "bidirectional"))
    )
    (net (code "92") (name "unconnected-(J4-PadP3)") (class "Default")
      (node (ref "J4") (pin "P3") (pinfunction "P3_P3") (pintype "passive"))
    )
    (net (code "93") (name "unconnected-(JP1-Pad7)") (class "Default")
      (node (ref "JP1") (pin "7") (pinfunction "7_7") (pintype "passive"))
    )
    (net (code "94") (name "unconnected-(JP1-Pad8)") (class "Default")
      (node (ref "JP1") (pin "8") (pinfunction "8_8") (pintype "passive"))
    )
    (net (code "95") (name "unconnected-(JP1-Pad9)") (class "Default")
      (node (ref "JP1") (pin "9") (pinfunction "9_9") (pintype "passive"))
    )
    (net (code "96") (name "unconnected-(JP1-Pad10)") (class "Default")
      (node (ref "JP1") (pin "10") (pinfunction "10_10") (pintype "passive"))
    )
    (net (code "97") (name "unconnected-(JP1-Pad11)") (class "Default")
      (node (ref "JP1") (pin "11") (pinfunction "11_11") (pintype "passive"))
    )
    (net (code "98") (name "unconnected-(JP1-Pad14)") (class "Default")
      (node (ref "JP1") (pin "14") (pinfunction "14_14") (pintype "passive"))
    )
    (net (code "99") (name "unconnected-(U2-P4-Pad4)") (class "Default")
      (node (ref "U2") (pin "4") (pinfunction "P4_4") (pintype "bidirectional"))
    )
    (net (code "100") (name "unconnected-(X2-CLK-Pad20)") (class "Default")
      (node (ref "X2") (pin "20") (pinfunction "CLK_20") (pintype "bidirectional"))
    )
    (net (code "101") (name "unconnected-(X2-CS-Pad17)") (class "Default")
      (node (ref "X2") (pin "17") (pinfunction "CS_17") (pintype "bidirectional"))
    )
    (net (code "102") (name "unconnected-(X2-DI-Pad21)") (class "Default")
      (node (ref "X2") (pin "21") (pinfunction "DI_21") (pintype "bidirectional"))
    )
    (net (code "103") (name "unconnected-(X2-DO-Pad18)") (class "Default")
      (node (ref "X2") (pin "18") (pinfunction "DO_18") (pintype "bidirectional"))
    )
    (net (code "104") (name "unconnected-(X2-GPIO9-Pad22)") (class "Default")
      (node (ref "X2") (pin "22") (pinfunction "GPIO9_22") (pintype "bidirectional"))
    )
    (net (code "105") (name "unconnected-(X2-GPIO10-Pad19)") (class "Default")
      (node (ref "X2") (pin "19") (pinfunction "GPIO10_19") (pintype "bidirectional"))
    )
    (net (code "106") (name "unconnected-(X3-CARD_DETECT-PadCD1)") (class "Default")
      (node (ref "X3") (pin "CD1") (pinfunction "CARD_DETECT_CD1") (pintype "passive"))
    )
    (net (code "107") (name "unconnected-(X3-CARD_DETECT1-PadCD2)") (class "Default")
      (node (ref "X3") (pin "CD2") (pinfunction "CARD_DETECT1_CD2") (pintype "passive"))
    )
    (net (code "108") (name "unconnected-(X3-DAT1-Pad8)") (class "Default")
      (node (ref "X3") (pin "8") (pinfunction "DAT1_8") (pintype "bidirectional"))
    )
    (net (code "109") (name "unconnected-(X3-DAT2-Pad1)") (class "Default")
      (node (ref "X3") (pin "1") (pinfunction "DAT2_1") (pintype "bidirectional"))
    )
    (net (code "110") (name "unconnected-(X4-PadID)") (class "Default")
      (node (ref "X4") (pin "ID") (pinfunction "ID_ID") (pintype "bidirectional"))
    )
  )
)
